# Sheet1.net
KiCad netlist of a schematic drawn in Altium Designer
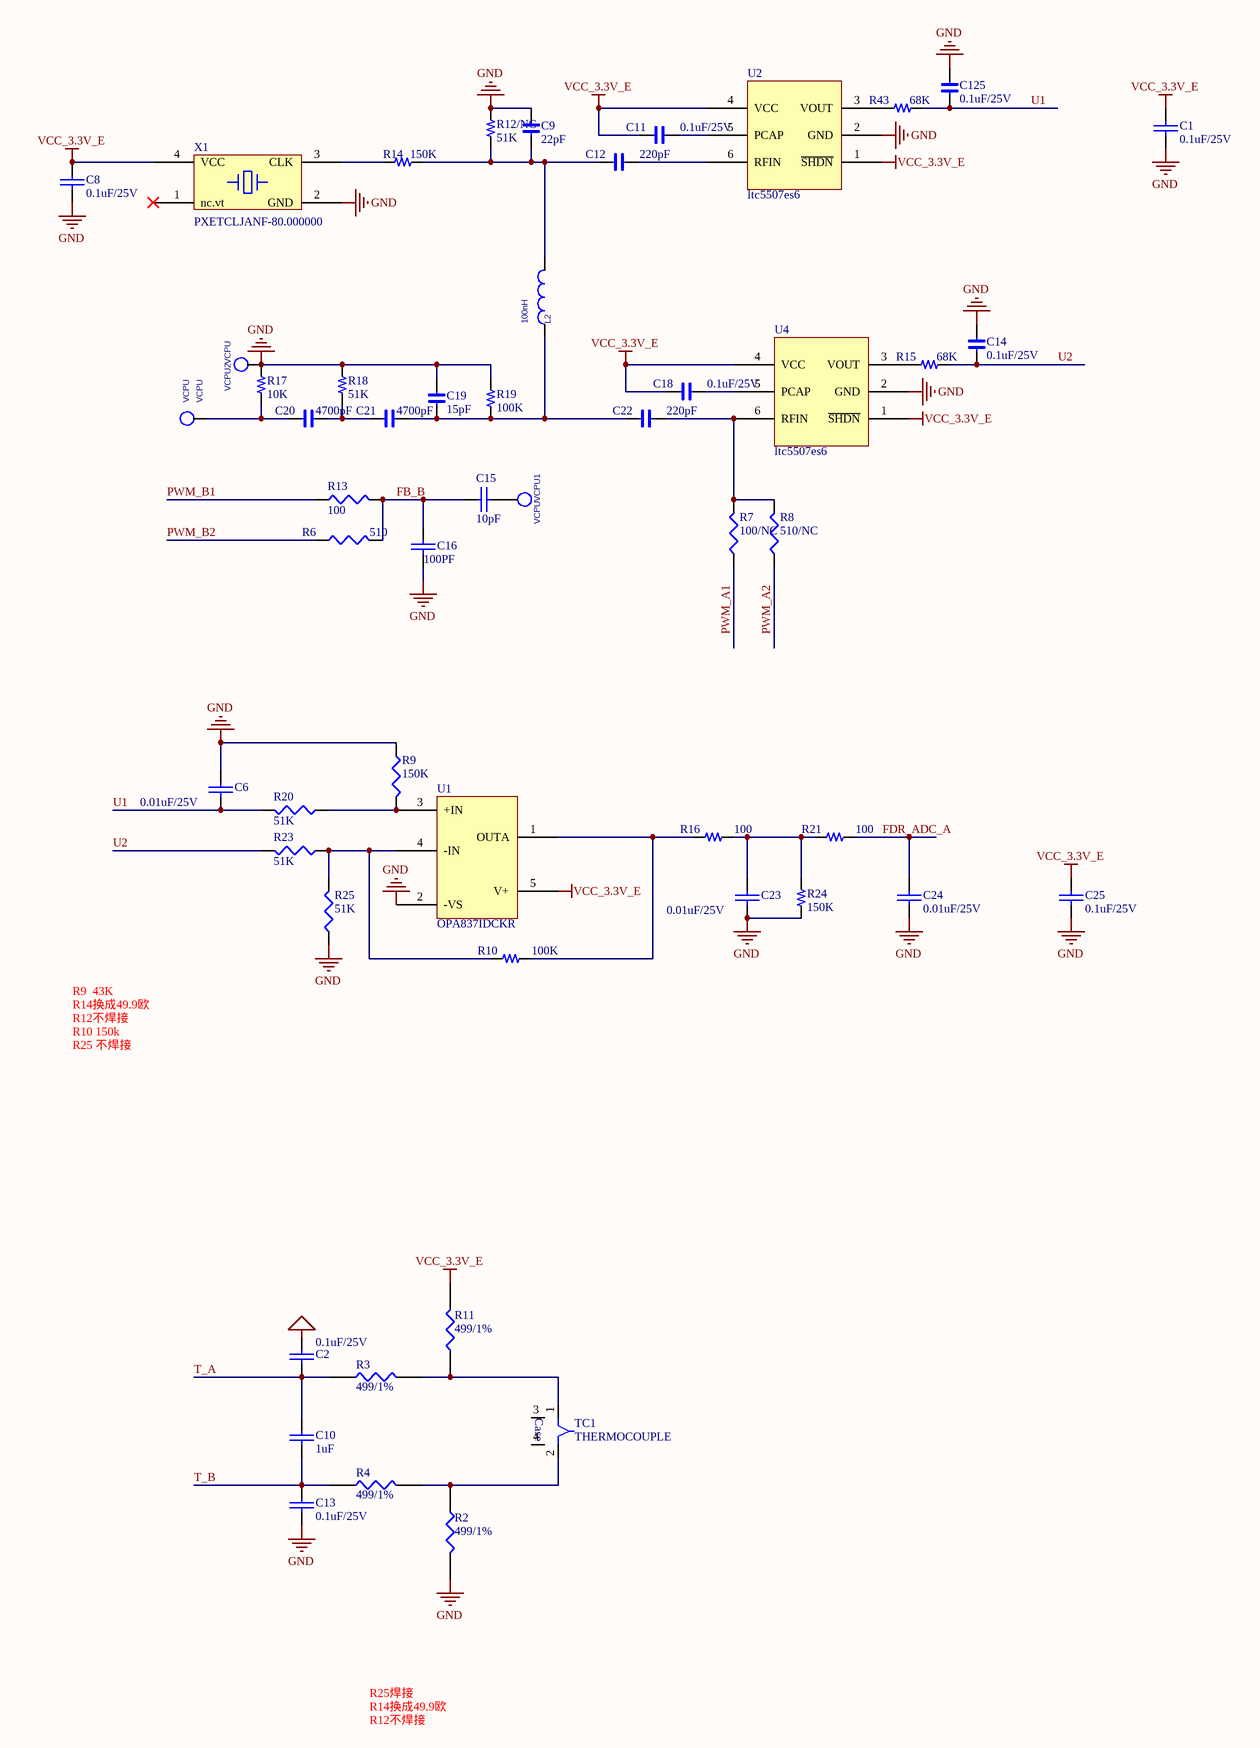
[diagram p0: Sheet1.SchDoc]

(export (version "E")
  (design (tool "Eeschema 10.0.6"))
  (components
    (comp (ref "C1")
      (value "0.1uF/25V")
      (footprint "0603C")
      (description "Capacitor")
      (libsource (lib "SM") (part "CAP"))
    )
    (comp (ref "C2")
      (value "0.1uF/25V")
      (footprint "0603c")
      (description "Capacitor")
      (libsource (lib "*") (part "CAP"))
    )
    (comp (ref "C6")
      (value "0.01uF/25V")
      (footprint "0603C")
      (description "Capacitor")
      (libsource (lib "SM") (part "CAP"))
    )
    (comp (ref "C8")
      (value "0.1uF/25V")
      (footprint "0603C")
      (description "Capacitor")
      (libsource (lib "SM") (part "CAP"))
    )
    (comp (ref "C9")
      (value "22pF")
      (footprint "0603C")
      (description "C")
      (libsource (lib "YxmSCH") (part "C"))
    )
    (comp (ref "C10")
      (value "1uF")
      (footprint "0603c")
      (description "Capacitor")
      (libsource (lib "*") (part "CAP"))
    )
    (comp (ref "C11")
      (value "0.1uF/25V")
      (footprint "0603C")
      (description "C")
      (libsource (lib "YxmSCH") (part "C"))
    )
    (comp (ref "C12")
      (value "220pF")
      (footprint "0603C")
      (description "C")
      (libsource (lib "YxmSCH") (part "C"))
    )
    (comp (ref "C13")
      (value "0.1uF/25V")
      (footprint "0603c")
      (description "Capacitor")
      (libsource (lib "*") (part "CAP"))
    )
    (comp (ref "C14")
      (value "0.1uF/25V")
      (footprint "0603C")
      (description "C")
      (libsource (lib "YxmSCH") (part "C"))
    )
    (comp (ref "C15")
      (value "10pF")
      (footprint "0603C")
      (description "Capacitor")
      (libsource (lib "SM") (part "CAP"))
    )
    (comp (ref "C16")
      (value "100PF")
      (footprint "0603C")
      (description "Capacitor")
      (libsource (lib "SM") (part "CAP"))
    )
    (comp (ref "C18")
      (value "0.1uF/25V")
      (footprint "0603C")
      (description "C")
      (libsource (lib "YxmSCH") (part "C"))
    )
    (comp (ref "C19")
      (value "15pF")
      (footprint "0603C")
      (description "C")
      (libsource (lib "YxmSCH") (part "C"))
    )
    (comp (ref "C20")
      (value "4700pF")
      (footprint "0603C")
      (description "C")
      (libsource (lib "YxmSCH") (part "C"))
    )
    (comp (ref "C21")
      (value "4700pF")
      (footprint "0603C")
      (description "C")
      (libsource (lib "YxmSCH") (part "C"))
    )
    (comp (ref "C22")
      (value "220pF")
      (footprint "0603C")
      (description "C")
      (libsource (lib "YxmSCH") (part "C"))
    )
    (comp (ref "C23")
      (value "0.01uF/25V")
      (footprint "0603C")
      (description "Capacitor")
      (libsource (lib "SM") (part "CAP"))
    )
    (comp (ref "C24")
      (value "0.01uF/25V")
      (footprint "0603C")
      (description "Capacitor")
      (libsource (lib "SM") (part "CAP"))
    )
    (comp (ref "C25")
      (value "0.1uF/25V")
      (footprint "0603C")
      (description "Capacitor")
      (libsource (lib "SM") (part "CAP"))
    )
    (comp (ref "C125")
      (value "0.1uF/25V")
      (footprint "0603C")
      (description "C")
      (libsource (lib "YxmSCH") (part "C"))
    )
    (comp (ref "L2") (value "100nH") (footprint "0603R") (libsource (lib "*") (part "INDUCTOR_1")))
    (comp (ref "R2") (value "499/1%") (footprint "0603r") (libsource (lib "*") (part "RES1")))
    (comp (ref "R3") (value "499/1%") (footprint "0603r") (libsource (lib "*") (part "RES1")))
    (comp (ref "R4") (value "499/1%") (footprint "0603r") (libsource (lib "*") (part "RES1")))
    (comp (ref "R6")
      (value "510")
      (footprint "0603R")
      (description "Resistor")
      (fields (field (name "PUBLISHER") "Altium Limited"))
      (libsource (lib "SM") (part "Res3"))
    )
    (comp (ref "R7")
      (value "100/NC")
      (footprint "0603R")
      (description "Resistor")
      (fields (field (name "PUBLISHER") "Altium Limited"))
      (libsource (lib "SM") (part "Res3"))
    )
    (comp (ref "R8")
      (value "510/NC")
      (footprint "0603R")
      (description "Resistor")
      (fields (field (name "PUBLISHER") "Altium Limited"))
      (libsource (lib "SM") (part "Res3"))
    )
    (comp (ref "R9")
      (value "150K")
      (footprint "0603R")
      (description "Resistor")
      (fields (field (name "PUBLISHER") "Altium Limited"))
      (libsource (lib "SM") (part "Res3"))
    )
    (comp (ref "R10")
      (value "100K")
      (footprint "0603R")
      (description "R")
      (libsource (lib "JRJ_1") (part "R"))
    )
    (comp (ref "R11") (value "499/1%") (footprint "0603r") (libsource (lib "*") (part "RES1")))
    (comp (ref "R12/NC")
      (value "51K")
      (footprint "0603r")
      (description "R")
      (libsource (lib "JRJ") (part "R"))
    )
    (comp (ref "R13")
      (value "100")
      (footprint "0603R")
      (description "Resistor")
      (fields (field (name "PUBLISHER") "Altium Limited"))
      (libsource (lib "SM") (part "Res3"))
    )
    (comp (ref "R14") (value "150K") (footprint "0603r") (description "R") (libsource (lib "JRJ") (part "R")))
    (comp (ref "R15") (value "68K") (footprint "0603r") (description "R") (libsource (lib "JRJ") (part "R")))
    (comp (ref "R16")
      (value "100")
      (footprint "0603R")
      (description "R")
      (libsource (lib "JRJ_1") (part "R"))
    )
    (comp (ref "R17") (value "10K") (footprint "0603r") (description "R") (libsource (lib "JRJ") (part "R")))
    (comp (ref "R18") (value "51K") (footprint "0603r") (description "R") (libsource (lib "JRJ") (part "R")))
    (comp (ref "R19") (value "100K") (footprint "0603r") (description "R") (libsource (lib "JRJ") (part "R")))
    (comp (ref "R20")
      (value "51K")
      (footprint "0603R")
      (description "Resistor")
      (fields (field (name "PUBLISHER") "Altium Limited"))
      (libsource (lib "SM") (part "Res3"))
    )
    (comp (ref "R21")
      (value "100")
      (footprint "0603R")
      (description "R")
      (libsource (lib "JRJ_1") (part "R"))
    )
    (comp (ref "R23")
      (value "51K")
      (footprint "0603R")
      (description "Resistor")
      (fields (field (name "PUBLISHER") "Altium Limited"))
      (libsource (lib "SM") (part "Res3"))
    )
    (comp (ref "R24")
      (value "150K")
      (footprint "0603R")
      (description "R")
      (libsource (lib "JRJ_1") (part "R"))
    )
    (comp (ref "R25")
      (value "51K")
      (footprint "0603R")
      (description "Resistor")
      (fields (field (name "PUBLISHER") "Altium Limited"))
      (libsource (lib "SM") (part "Res3"))
    )
    (comp (ref "R43") (value "68K") (footprint "0603r") (description "R") (libsource (lib "JRJ") (part "R")))
    (comp (ref "TC1") (value "THERMOCOUPLE") (footprint "0603R") (libsource (lib "*") (part "THERMOCOUPLE")))
    (comp (ref "U1")
      (value "OPA837IDCKR")
      (footprint "SC70-5")
      (libsource (lib "Schlib_20110825") (part "OPA837 DCK"))
    )
    (comp (ref "U2") (value "ltc5507es6") (footprint "SOT23-6") (libsource (lib "stm32") (part "ltc5507es6")))
    (comp (ref "U4") (value "ltc5507es6") (footprint "SOT23-6") (libsource (lib "stm32") (part "ltc5507es6")))
    (comp (ref "VCPU") (value "VCPU") (footprint "probe") (libsource (lib "*") (part "T_POINT_R")))
    (comp (ref "VCPU1") (value "VCPU") (footprint "probe") (libsource (lib "*") (part "T_POINT_R")))
    (comp (ref "VCPU2") (value "VCPU") (footprint "probe") (libsource (lib "*") (part "T_POINT_R")))
    (comp (ref "X1")
      (value "PXETCLJANF-80.000000")
      (footprint "XTAL4TN_7050")
      (libsource (lib "Y0801_V13") (part "XTAL4S"))
    )
  )
  (nets
    (net (code "1") (name "/FB_B") (class "Default")
      (node (ref "C15") (pin "1") (pinfunction "1_1") (pintype "passive"))
      (node (ref "C16") (pin "1") (pinfunction "1_1") (pintype "passive"))
      (node (ref "R13") (pin "2") (pinfunction "2_2") (pintype "passive"))
      (node (ref "R6") (pin "2") (pinfunction "2_2") (pintype "passive"))
    )
    (net (code "2") (name "/FDR_ADC_A") (class "Default")
      (node (ref "C24") (pin "2") (pinfunction "2_2") (pintype "passive"))
      (node (ref "R21") (pin "2") (pintype "passive"))
    )
    (net (code "3") (name "/PWM_A1") (class "Default")
      (node (ref "R7") (pin "1") (pinfunction "1_1") (pintype "passive"))
    )
    (net (code "4") (name "/PWM_A2") (class "Default")
      (node (ref "R8") (pin "1") (pinfunction "1_1") (pintype "passive"))
    )
    (net (code "5") (name "/PWM_B1") (class "Default")
      (node (ref "R13") (pin "1") (pinfunction "1_1") (pintype "passive"))
    )
    (net (code "6") (name "/PWM_B2") (class "Default")
      (node (ref "R6") (pin "1") (pinfunction "1_1") (pintype "passive"))
    )
    (net (code "7") (name "/T_A") (class "Default")
      (node (ref "C10") (pin "1") (pinfunction "1_1") (pintype "passive"))
      (node (ref "C2") (pin "1") (pinfunction "1_1") (pintype "passive"))
      (node (ref "R3") (pin "1") (pinfunction "1_1") (pintype "passive"))
    )
    (net (code "8") (name "/T_B") (class "Default")
      (node (ref "C10") (pin "2") (pinfunction "2_2") (pintype "passive"))
      (node (ref "C13") (pin "1") (pinfunction "1_1") (pintype "passive"))
      (node (ref "R4") (pin "1") (pinfunction "1_1") (pintype "passive"))
    )
    (net (code "9") (name "/U1") (class "Default")
      (node (ref "C125") (pin "1") (pintype "passive"))
      (node (ref "C6") (pin "1") (pinfunction "1_1") (pintype "passive"))
      (node (ref "R20") (pin "2") (pinfunction "2_2") (pintype "passive"))
      (node (ref "R43") (pin "1") (pintype "passive"))
    )
    (net (code "10") (name "/U2") (class "Default")
      (node (ref "C14") (pin "1") (pintype "passive"))
      (node (ref "R15") (pin "1") (pintype "passive"))
      (node (ref "R23") (pin "2") (pinfunction "2_2") (pintype "passive"))
    )
    (net (code "11") (name "GND") (class "Default")
      (node (ref "C1") (pin "1") (pinfunction "1_1") (pintype "passive"))
      (node (ref "C125") (pin "2") (pintype "passive"))
      (node (ref "C13") (pin "2") (pinfunction "2_2") (pintype "passive"))
      (node (ref "C14") (pin "2") (pintype "passive"))
      (node (ref "C16") (pin "2") (pinfunction "2_2") (pintype "passive"))
      (node (ref "C19") (pin "2") (pintype "passive"))
      (node (ref "C2") (pin "2") (pinfunction "2_2") (pintype "passive"))
      (node (ref "C23") (pin "1") (pinfunction "1_1") (pintype "passive"))
      (node (ref "C24") (pin "1") (pinfunction "1_1") (pintype "passive"))
      (node (ref "C25") (pin "1") (pinfunction "1_1") (pintype "passive"))
      (node (ref "C6") (pin "2") (pinfunction "2_2") (pintype "passive"))
      (node (ref "C8") (pin "2") (pinfunction "2_2") (pintype "passive"))
      (node (ref "C9") (pin "1") (pintype "passive"))
      (node (ref "R12/NC") (pin "2") (pintype "passive"))
      (node (ref "R17") (pin "2") (pintype "passive"))
      (node (ref "R18") (pin "2") (pintype "passive"))
      (node (ref "R19") (pin "2") (pintype "passive"))
      (node (ref "R2") (pin "2") (pinfunction "2_2") (pintype "passive"))
      (node (ref "R24") (pin "1") (pintype "passive"))
      (node (ref "R25") (pin "1") (pinfunction "1_1") (pintype "passive"))
      (node (ref "R9") (pin "1") (pinfunction "1_1") (pintype "passive"))
      (node (ref "U1") (pin "2") (pinfunction "-VS_2") (pintype "passive"))
      (node (ref "U2") (pin "2") (pinfunction "GND_2") (pintype "passive"))
      (node (ref "U4") (pin "2") (pinfunction "GND_2") (pintype "passive"))
      (node (ref "VCPU2") (pin "1") (pinfunction "TP_1") (pintype "passive"))
      (node (ref "X1") (pin "2") (pinfunction "GND_2") (pintype "power_in"))
    )
    (net (code "12") (name "Net-(C12-Pad1)") (class "Default")
      (node (ref "C12") (pin "1") (pintype "passive"))
      (node (ref "C9") (pin "2") (pintype "passive"))
      (node (ref "L2") (pin "2") (pinfunction "2_2") (pintype "passive"))
      (node (ref "R12/NC") (pin "1") (pintype "passive"))
      (node (ref "R14") (pin "2") (pintype "passive"))
    )
    (net (code "13") (name "Net-(C19-Pad1)") (class "Default")
      (node (ref "C19") (pin "1") (pintype "passive"))
      (node (ref "C21") (pin "2") (pintype "passive"))
      (node (ref "C22") (pin "1") (pintype "passive"))
      (node (ref "L2") (pin "1") (pinfunction "1_1") (pintype "passive"))
      (node (ref "R19") (pin "1") (pintype "passive"))
    )
    (net (code "14") (name "Net-(C20-Pad2)") (class "Default")
      (node (ref "C20") (pin "2") (pintype "passive"))
      (node (ref "C21") (pin "1") (pintype "passive"))
      (node (ref "R18") (pin "1") (pintype "passive"))
    )
    (net (code "15") (name "Net-(C23-Pad2)") (class "Default")
      (node (ref "C23") (pin "2") (pinfunction "2_2") (pintype "passive"))
      (node (ref "R16") (pin "2") (pintype "passive"))
      (node (ref "R21") (pin "1") (pintype "passive"))
      (node (ref "R24") (pin "2") (pintype "passive"))
    )
    (net (code "16") (name "Net-(R2-Pad1)") (class "Default")
      (node (ref "R2") (pin "1") (pinfunction "1_1") (pintype "passive"))
      (node (ref "R4") (pin "2") (pinfunction "2_2") (pintype "passive"))
      (node (ref "TC1") (pin "2") (pinfunction "2_2") (pintype "passive"))
    )
    (net (code "17") (name "Net-(R11-Pad1)") (class "Default")
      (node (ref "R11") (pin "1") (pinfunction "1_1") (pintype "passive"))
      (node (ref "R3") (pin "2") (pinfunction "2_2") (pintype "passive"))
      (node (ref "TC1") (pin "1") (pinfunction "1_1") (pintype "passive"))
    )
    (net (code "18") (name "Net-(U1-+IN)") (class "Default")
      (node (ref "R20") (pin "1") (pinfunction "1_1") (pintype "passive"))
      (node (ref "R9") (pin "2") (pinfunction "2_2") (pintype "passive"))
      (node (ref "U1") (pin "3") (pinfunction "+IN_3") (pintype "passive"))
    )
    (net (code "19") (name "Net-(U1--IN)") (class "Default")
      (node (ref "R10") (pin "1") (pintype "passive"))
      (node (ref "R23") (pin "1") (pinfunction "1_1") (pintype "passive"))
      (node (ref "R25") (pin "2") (pinfunction "2_2") (pintype "passive"))
      (node (ref "U1") (pin "4") (pinfunction "-IN_4") (pintype "passive"))
    )
    (net (code "20") (name "Net-(U1-OUTA)") (class "Default")
      (node (ref "R10") (pin "2") (pintype "passive"))
      (node (ref "R16") (pin "1") (pintype "passive"))
      (node (ref "U1") (pin "1") (pinfunction "OUTA_1") (pintype "passive"))
    )
    (net (code "21") (name "Net-(U2-PCAP)") (class "Default")
      (node (ref "C11") (pin "2") (pintype "passive"))
      (node (ref "U2") (pin "5") (pinfunction "PCAP_5") (pintype "passive"))
    )
    (net (code "22") (name "Net-(U2-RFIN)") (class "Default")
      (node (ref "C12") (pin "2") (pintype "passive"))
      (node (ref "U2") (pin "6") (pinfunction "RFIN_6") (pintype "passive"))
    )
    (net (code "23") (name "Net-(U2-VOUT)") (class "Default")
      (node (ref "R43") (pin "2") (pintype "passive"))
      (node (ref "U2") (pin "3") (pinfunction "VOUT_3") (pintype "passive"))
    )
    (net (code "24") (name "Net-(U4-PCAP)") (class "Default")
      (node (ref "C18") (pin "2") (pintype "passive"))
      (node (ref "U4") (pin "5") (pinfunction "PCAP_5") (pintype "passive"))
    )
    (net (code "25") (name "Net-(U4-RFIN)") (class "Default")
      (node (ref "C22") (pin "2") (pintype "passive"))
      (node (ref "R7") (pin "2") (pinfunction "2_2") (pintype "passive"))
      (node (ref "R8") (pin "2") (pinfunction "2_2") (pintype "passive"))
      (node (ref "U4") (pin "6") (pinfunction "RFIN_6") (pintype "passive"))
    )
    (net (code "26") (name "Net-(U4-VOUT)") (class "Default")
      (node (ref "R15") (pin "2") (pintype "passive"))
      (node (ref "U4") (pin "3") (pinfunction "VOUT_3") (pintype "passive"))
    )
    (net (code "27") (name "Net-(VCPU-TP)") (class "Default")
      (node (ref "C20") (pin "1") (pintype "passive"))
      (node (ref "R17") (pin "1") (pintype "passive"))
      (node (ref "VCPU") (pin "1") (pinfunction "TP_1") (pintype "passive"))
    )
    (net (code "28") (name "Net-(VCPU1-TP)") (class "Default")
      (node (ref "C15") (pin "2") (pinfunction "2_2") (pintype "passive"))
      (node (ref "VCPU1") (pin "1") (pinfunction "TP_1") (pintype "passive"))
    )
    (net (code "29") (name "Net-(X1-CLK)") (class "Default")
      (node (ref "R14") (pin "1") (pintype "passive"))
      (node (ref "X1") (pin "3") (pinfunction "CLK_3") (pintype "passive"))
    )
    (net (code "30") (name "VCC_3.3V_E") (class "Default")
      (node (ref "C1") (pin "2") (pinfunction "2_2") (pintype "passive"))
      (node (ref "C11") (pin "1") (pintype "passive"))
      (node (ref "C18") (pin "1") (pintype "passive"))
      (node (ref "C25") (pin "2") (pinfunction "2_2") (pintype "passive"))
      (node (ref "C8") (pin "1") (pinfunction "1_1") (pintype "passive"))
      (node (ref "R11") (pin "2") (pinfunction "2_2") (pintype "passive"))
      (node (ref "U1") (pin "5") (pinfunction "V+_5") (pintype "passive"))
      (node (ref "U2") (pin "1") (pinfunction "~{SHDN}_1") (pintype "passive"))
      (node (ref "U2") (pin "4") (pinfunction "VCC_4") (pintype "passive"))
      (node (ref "U4") (pin "1") (pinfunction "~{SHDN}_1") (pintype "passive"))
      (node (ref "U4") (pin "4") (pinfunction "VCC_4") (pintype "passive"))
      (node (ref "X1") (pin "4") (pinfunction "VCC_4") (pintype "power_in"))
    )
    (net (code "31") (name "unconnected-(TC1-Pad3)") (class "Default")
      (node (ref "TC1") (pin "3") (pinfunction "3_3") (pintype "passive"))
    )
    (net (code "32") (name "unconnected-(TC1-Pad4)") (class "Default")
      (node (ref "TC1") (pin "4") (pinfunction "4_4") (pintype "passive"))
    )
    (net (code "33") (name "unconnected-(X1-nc.vt-Pad1)") (class "Default")
      (node (ref "X1") (pin "1") (pinfunction "nc.vt_1") (pintype "passive+no_connect"))
    )
  )
)
